# LM13700_v2.net
KiCad netlist of a schematic drawn in EAGLE
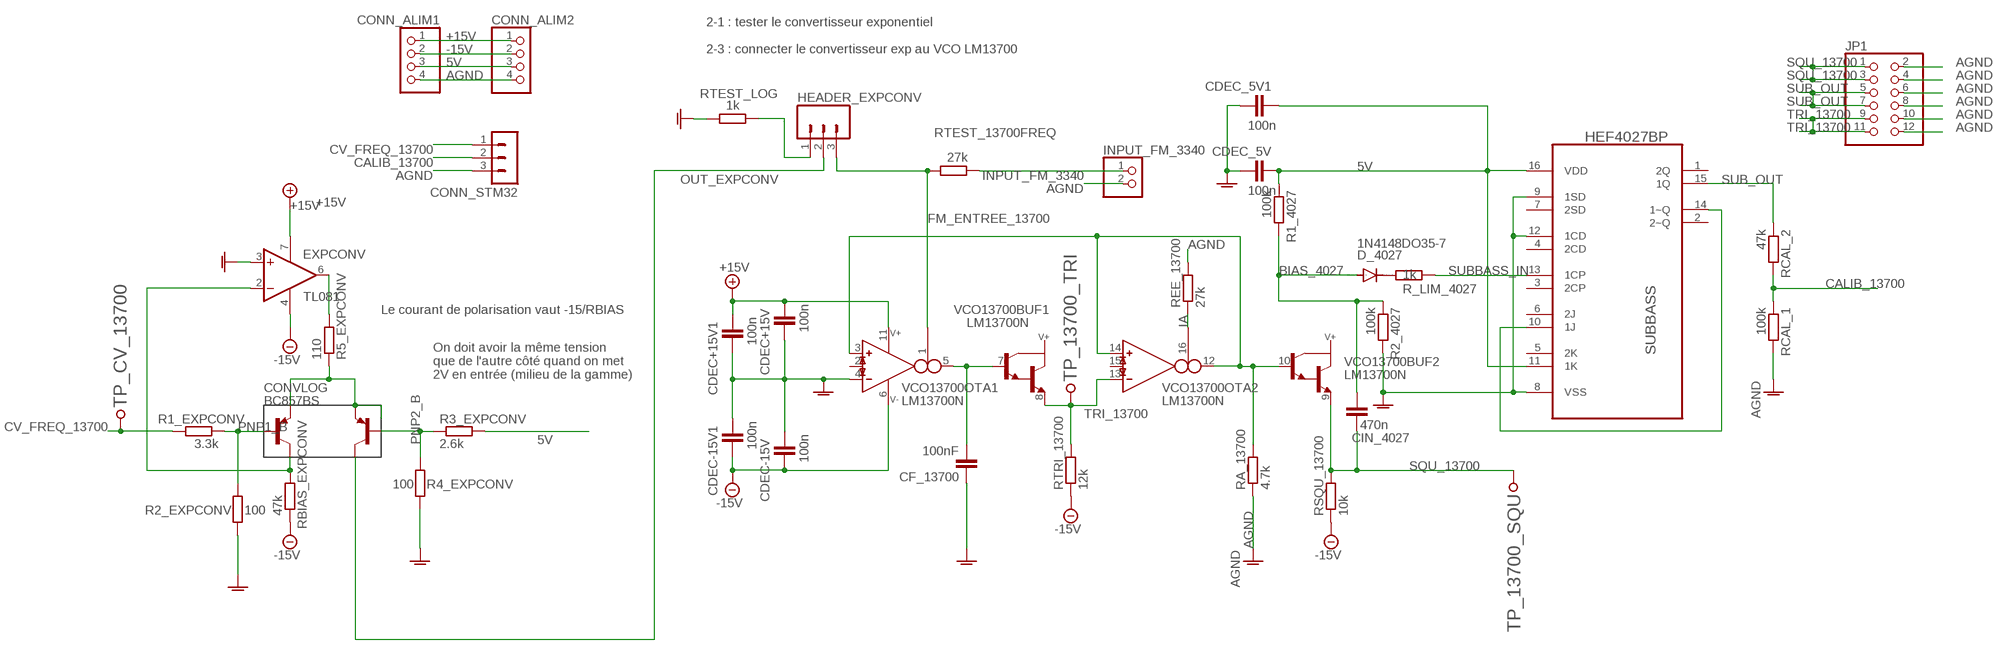
[diagram p0: schematic, sheet 1]

(export (version "E")
  (design (tool "Eeschema 10.0.6"))
  (components
    (comp (ref "CDEC+15V")
      (value "100n")
      (footprint "eagle-import:C075-032X103")
      (libsource (lib "eagle-import") (part "C-EU075-032X103"))
    )
    (comp (ref "CDEC+15V1")
      (value "100n")
      (footprint "eagle-import:C050-025X075")
      (libsource (lib "eagle-import") (part "C-EU050-025X075"))
    )
    (comp (ref "CDEC-15V")
      (value "100n")
      (footprint "eagle-import:C050-025X075")
      (libsource (lib "eagle-import") (part "C-EU050-025X075"))
    )
    (comp (ref "CDEC-15V1")
      (value "100n")
      (footprint "eagle-import:C075-032X103")
      (libsource (lib "eagle-import") (part "C-EU075-032X103"))
    )
    (comp (ref "CDEC_5V")
      (value "100n")
      (footprint "eagle-import:C050-025X075")
      (libsource (lib "eagle-import") (part "C-EU050-025X075"))
    )
    (comp (ref "CDEC_5V1")
      (value "100n")
      (footprint "eagle-import:C050-025X075")
      (libsource (lib "eagle-import") (part "C-EU050-025X075"))
    )
    (comp (ref "CF_13700")
      (value "100nF")
      (footprint "eagle-import:C050-025X075")
      (libsource (lib "eagle-import") (part "C-EU050-025X075"))
    )
    (comp (ref "CIN_4027")
      (value "470n")
      (footprint "eagle-import:C050-025X075")
      (libsource (lib "eagle-import") (part "C-EU050-025X075"))
    )
    (comp (ref "CONN_ALIM1")
      (value "PINHD-1X4")
      (footprint "eagle-import:1X04")
      (libsource (lib "eagle-import") (part "PINHD-1X4"))
    )
    (comp (ref "CONN_ALIM2")
      (value "PINHD-1X4")
      (footprint "eagle-import:1X04")
      (libsource (lib "eagle-import") (part "PINHD-1X4"))
    )
    (comp (ref "CONN_STM32")
      (value "MA03-1")
      (footprint "eagle-import:MA03-1")
      (libsource (lib "eagle-import") (part "MA03-1"))
    )
    (comp (ref "CONVLOG")
      (value "BC857BS")
      (footprint "eagle-import:DIL06")
      (libsource (lib "eagle-import") (part "BC857BS"))
    )
    (comp (ref "D_4027")
      (value "1N4148DO35-7")
      (footprint "eagle-import:DO35-7")
      (libsource (lib "eagle-import") (part "1N4148DO35-7"))
    )
    (comp (ref "EXPCONV")
      (value "TL081")
      (footprint "eagle-import:DIL08")
      (libsource (lib "eagle-import") (part "1AMP_P7+4N"))
    )
    (comp (ref "HEADER_EXPCONV")
      (value "M03")
      (footprint "eagle-import:03P")
      (libsource (lib "eagle-import") (part "M03"))
    )
    (comp (ref "INPUT_FM_3340")
      (value "PINHD-1X2")
      (footprint "eagle-import:1X02")
      (libsource (lib "eagle-import") (part "PINHD-1X2"))
    )
    (comp (ref "JP1")
      (value "PINHD-2X6")
      (footprint "eagle-import:2X06")
      (libsource (lib "eagle-import") (part "PINHD-2X6"))
    )
    (comp (ref "R1_4027")
      (value "100k")
      (footprint "eagle-import:0204_7")
      (libsource (lib "eagle-import") (part "R-EU_0204/7"))
    )
    (comp (ref "R1_EXPCONV")
      (value "3.3k")
      (footprint "eagle-import:0204_7")
      (libsource (lib "eagle-import") (part "R-EU_0204/7"))
    )
    (comp (ref "R2_4027")
      (value "100k")
      (footprint "eagle-import:0204_7")
      (libsource (lib "eagle-import") (part "R-EU_0204/7"))
    )
    (comp (ref "R2_EXPCONV")
      (value "100")
      (footprint "eagle-import:0204_7")
      (libsource (lib "eagle-import") (part "R-EU_0204/7"))
    )
    (comp (ref "R3_EXPCONV")
      (value "2.6k")
      (footprint "eagle-import:0204_7")
      (libsource (lib "eagle-import") (part "R-EU_0204/7"))
    )
    (comp (ref "R4_EXPCONV")
      (value "100")
      (footprint "eagle-import:0204_7")
      (libsource (lib "eagle-import") (part "R-EU_0204/7"))
    )
    (comp (ref "R5_EXPCONV")
      (value "110")
      (footprint "eagle-import:0204_7")
      (libsource (lib "eagle-import") (part "R-EU_0204/7"))
    )
    (comp (ref "RA_13700")
      (value "4.7k")
      (footprint "eagle-import:0204_7")
      (libsource (lib "eagle-import") (part "R-EU_0204/7"))
    )
    (comp (ref "RBIAS_EXPCONV")
      (value "47k")
      (footprint "eagle-import:0204_7")
      (libsource (lib "eagle-import") (part "R-EU_0204/7"))
    )
    (comp (ref "RCAL_1")
      (value "100k")
      (footprint "eagle-import:0204_7")
      (libsource (lib "eagle-import") (part "R-EU_0204/7"))
    )
    (comp (ref "RCAL_2")
      (value "47k")
      (footprint "eagle-import:0204_7")
      (libsource (lib "eagle-import") (part "R-EU_0204/7"))
    )
    (comp (ref "REE_13700")
      (value "27k")
      (footprint "eagle-import:0204_7")
      (libsource (lib "eagle-import") (part "R-EU_0204/7"))
    )
    (comp (ref "RSQU_13700")
      (value "10k")
      (footprint "eagle-import:0204_7")
      (libsource (lib "eagle-import") (part "R-EU_0204/7"))
    )
    (comp (ref "RTEST_13700FREQ")
      (value "27k")
      (footprint "eagle-import:0204_7")
      (libsource (lib "eagle-import") (part "R-EU_0204/7"))
    )
    (comp (ref "RTEST_LOG")
      (value "1k")
      (footprint "eagle-import:0204_7")
      (libsource (lib "eagle-import") (part "R-EU_0204/7"))
    )
    (comp (ref "RTRI_13700")
      (value "12k")
      (footprint "eagle-import:0204_7")
      (libsource (lib "eagle-import") (part "R-EU_0204/7"))
    )
    (comp (ref "R_LIM_4027")
      (value "1k")
      (footprint "eagle-import:0204_7")
      (libsource (lib "eagle-import") (part "R-EU_0204/7"))
    )
    (comp (ref "SUBBASS")
      (value "HEF4027BP")
      (footprint "eagle-import:DIP254P762X420-16")
      (fields (field (name "MF") "NXP Semiconductors"))
      (libsource (lib "eagle-import") (part "HEF4027BP"))
    )
    (comp (ref "TP_13700_SQU")
      (value "TESTPOINT")
      (footprint "eagle-import:TESTPOINT_63")
      (libsource (lib "eagle-import") (part "TESTPOINT"))
    )
    (comp (ref "TP_13700_TRI")
      (value "TESTPOINT")
      (footprint "eagle-import:TESTPOINT_63")
      (libsource (lib "eagle-import") (part "TESTPOINT"))
    )
    (comp (ref "TP_CV_13700")
      (value "TESTPOINT")
      (footprint "eagle-import:TESTPOINT_63")
      (libsource (lib "eagle-import") (part "TESTPOINT"))
    )
    (comp (ref "VCO13700")
      (value "LM13700N")
      (footprint "eagle-import:DIL16")
      (libsource (lib "eagle-import") (part "LM13700N"))
    )
  )
  (nets
    (net (code "1") (name "+15V") (class "Default")
      (node (ref "CDEC+15V") (pin "1") (pinfunction "1_1") (pintype "passive"))
      (node (ref "CDEC+15V1") (pin "1") (pinfunction "1_1") (pintype "passive"))
      (node (ref "CONN_ALIM1") (pin "1") (pinfunction "1_1") (pintype "passive"))
      (node (ref "CONN_ALIM2") (pin "1") (pinfunction "1_1") (pintype "passive"))
      (node (ref "EXPCONV") (pin "7") (pinfunction "V+_7") (pintype "power_in"))
      (node (ref "VCO13700") (pin "11") (pinfunction "V+_11") (pintype "power_in"))
    )
    (net (code "2") (name "-15V") (class "Default")
      (node (ref "CDEC-15V") (pin "2") (pinfunction "2_2") (pintype "passive"))
      (node (ref "CDEC-15V1") (pin "2") (pinfunction "2_2") (pintype "passive"))
      (node (ref "CONN_ALIM1") (pin "2") (pinfunction "2_2") (pintype "passive"))
      (node (ref "CONN_ALIM2") (pin "2") (pinfunction "2_2") (pintype "passive"))
      (node (ref "EXPCONV") (pin "4") (pinfunction "V-_4") (pintype "power_in"))
      (node (ref "RBIAS_EXPCONV") (pin "1") (pinfunction "1_1") (pintype "passive"))
      (node (ref "RSQU_13700") (pin "1") (pinfunction "1_1") (pintype "passive"))
      (node (ref "RTRI_13700") (pin "1") (pinfunction "1_1") (pintype "passive"))
      (node (ref "VCO13700") (pin "6") (pinfunction "V-_6") (pintype "power_in"))
    )
    (net (code "3") (name "/5V") (class "Default")
      (node (ref "CDEC_5V") (pin "1") (pinfunction "1_1") (pintype "passive"))
      (node (ref "CDEC_5V1") (pin "1") (pinfunction "1_1") (pintype "passive"))
      (node (ref "CONN_ALIM1") (pin "3") (pinfunction "3_3") (pintype "passive"))
      (node (ref "CONN_ALIM2") (pin "3") (pinfunction "3_3") (pintype "passive"))
      (node (ref "R1_4027") (pin "1") (pinfunction "1_1") (pintype "passive"))
      (node (ref "R3_EXPCONV") (pin "2") (pinfunction "2_2") (pintype "passive"))
      (node (ref "SUBBASS") (pin "11") (pinfunction "1K_11") (pintype "input"))
      (node (ref "SUBBASS") (pin "16") (pinfunction "VDD_16") (pintype "power_in"))
    )
    (net (code "4") (name "/BIAS_4027") (class "Default")
      (node (ref "CIN_4027") (pin "1") (pinfunction "1_1") (pintype "passive"))
      (node (ref "D_4027") (pin "A") (pinfunction "A_A") (pintype "passive"))
      (node (ref "R1_4027") (pin "2") (pinfunction "2_2") (pintype "passive"))
      (node (ref "R2_4027") (pin "1") (pinfunction "1_1") (pintype "passive"))
    )
    (net (code "5") (name "/CALIB_13700") (class "Default")
      (node (ref "CONN_STM32") (pin "2") (pinfunction "2_2") (pintype "passive"))
      (node (ref "RCAL_1") (pin "1") (pinfunction "1_1") (pintype "passive"))
      (node (ref "RCAL_2") (pin "2") (pinfunction "2_2") (pintype "passive"))
    )
    (net (code "6") (name "/CV_FREQ_13700") (class "Default")
      (node (ref "CONN_STM32") (pin "1") (pinfunction "1_1") (pintype "passive"))
      (node (ref "R1_EXPCONV") (pin "2") (pinfunction "2_2") (pintype "passive"))
      (node (ref "TP_CV_13700") (pin "P$1") (pinfunction "P$1_P$1") (pintype "passive"))
    )
    (net (code "7") (name "/FM_ENTREE_13700") (class "Default")
      (node (ref "HEADER_EXPCONV") (pin "3") (pinfunction "3_3") (pintype "passive"))
      (node (ref "RTEST_13700FREQ") (pin "2") (pinfunction "2_2") (pintype "passive"))
      (node (ref "VCO13700") (pin "1") (pinfunction "I_BIAS_1") (pintype "input"))
    )
    (net (code "8") (name "/IA") (class "Default")
      (node (ref "REE_13700") (pin "1") (pinfunction "1_1") (pintype "passive"))
      (node (ref "VCO13700") (pin "16") (pinfunction "I_BIAS_16") (pintype "input"))
    )
    (net (code "9") (name "/INPUT_FM_3340") (class "Default")
      (node (ref "INPUT_FM_3340") (pin "1") (pinfunction "1_1") (pintype "passive"))
      (node (ref "RTEST_13700FREQ") (pin "1") (pinfunction "1_1") (pintype "passive"))
    )
    (net (code "10") (name "/OUT_EXPCONV") (class "Default")
      (node (ref "CONVLOG") (pin "3") (pinfunction "C2_3") (pintype "passive"))
      (node (ref "HEADER_EXPCONV") (pin "2") (pinfunction "2_2") (pintype "passive"))
    )
    (net (code "11") (name "/PNP1_B") (class "Default")
      (node (ref "CONVLOG") (pin "2") (pinfunction "B1_2") (pintype "passive"))
      (node (ref "R1_EXPCONV") (pin "1") (pinfunction "1_1") (pintype "passive"))
      (node (ref "R2_EXPCONV") (pin "1") (pinfunction "1_1") (pintype "passive"))
    )
    (net (code "12") (name "/PNP2_B") (class "Default")
      (node (ref "CONVLOG") (pin "5") (pinfunction "B2_5") (pintype "passive"))
      (node (ref "R3_EXPCONV") (pin "1") (pinfunction "1_1") (pintype "passive"))
      (node (ref "R4_EXPCONV") (pin "1") (pinfunction "1_1") (pintype "passive"))
    )
    (net (code "13") (name "/SQU_13700") (class "Default")
      (node (ref "CIN_4027") (pin "2") (pinfunction "2_2") (pintype "passive"))
      (node (ref "JP1") (pin "1") (pinfunction "1_1") (pintype "passive"))
      (node (ref "JP1") (pin "3") (pinfunction "3_3") (pintype "passive"))
      (node (ref "RSQU_13700") (pin "2") (pinfunction "2_2") (pintype "passive"))
      (node (ref "TP_13700_SQU") (pin "P$1") (pinfunction "P$1_P$1") (pintype "passive"))
      (node (ref "VCO13700") (pin "9") (pinfunction "E_9") (pintype "passive"))
    )
    (net (code "14") (name "/SUBBASS_IN") (class "Default")
      (node (ref "R_LIM_4027") (pin "1") (pinfunction "1_1") (pintype "passive"))
      (node (ref "SUBBASS") (pin "13") (pinfunction "1CP_13") (pintype "input"))
    )
    (net (code "15") (name "/SUB_OUT") (class "Default")
      (node (ref "JP1") (pin "5") (pinfunction "5_5") (pintype "passive"))
      (node (ref "JP1") (pin "7") (pinfunction "7_7") (pintype "passive"))
      (node (ref "RCAL_2") (pin "1") (pinfunction "1_1") (pintype "passive"))
      (node (ref "SUBBASS") (pin "15") (pinfunction "1Q_15") (pintype "output"))
    )
    (net (code "16") (name "/TRI_13700") (class "Default")
      (node (ref "JP1") (pin "11") (pinfunction "11_11") (pintype "passive"))
      (node (ref "JP1") (pin "9") (pinfunction "9_9") (pintype "passive"))
      (node (ref "RTRI_13700") (pin "2") (pinfunction "2_2") (pintype "passive"))
      (node (ref "TP_13700_TRI") (pin "P$1") (pinfunction "P$1_P$1") (pintype "passive"))
      (node (ref "VCO13700") (pin "13") (pinfunction "IN_N_13") (pintype "input"))
      (node (ref "VCO13700") (pin "8") (pinfunction "E_8") (pintype "passive"))
    )
    (net (code "17") (name "AGND") (class "Default")
      (node (ref "CDEC+15V") (pin "2") (pinfunction "2_2") (pintype "passive"))
      (node (ref "CDEC+15V1") (pin "2") (pinfunction "2_2") (pintype "passive"))
      (node (ref "CDEC-15V") (pin "1") (pinfunction "1_1") (pintype "passive"))
      (node (ref "CDEC-15V1") (pin "1") (pinfunction "1_1") (pintype "passive"))
      (node (ref "CDEC_5V") (pin "2") (pinfunction "2_2") (pintype "passive"))
      (node (ref "CDEC_5V1") (pin "2") (pinfunction "2_2") (pintype "passive"))
      (node (ref "CF_13700") (pin "1") (pinfunction "1_1") (pintype "passive"))
      (node (ref "CONN_ALIM1") (pin "4") (pinfunction "4_4") (pintype "passive"))
      (node (ref "CONN_ALIM2") (pin "4") (pinfunction "4_4") (pintype "passive"))
      (node (ref "CONN_STM32") (pin "3") (pinfunction "3_3") (pintype "passive"))
      (node (ref "EXPCONV") (pin "3") (pinfunction "+IN_3") (pintype "input"))
      (node (ref "INPUT_FM_3340") (pin "2") (pinfunction "2_2") (pintype "passive"))
      (node (ref "JP1") (pin "10") (pinfunction "10_10") (pintype "passive"))
      (node (ref "JP1") (pin "12") (pinfunction "12_12") (pintype "passive"))
      (node (ref "JP1") (pin "2") (pinfunction "2_2") (pintype "passive"))
      (node (ref "JP1") (pin "4") (pinfunction "4_4") (pintype "passive"))
      (node (ref "JP1") (pin "6") (pinfunction "6_6") (pintype "passive"))
      (node (ref "JP1") (pin "8") (pinfunction "8_8") (pintype "passive"))
      (node (ref "R2_4027") (pin "2") (pinfunction "2_2") (pintype "passive"))
      (node (ref "R2_EXPCONV") (pin "2") (pinfunction "2_2") (pintype "passive"))
      (node (ref "R4_EXPCONV") (pin "2") (pinfunction "2_2") (pintype "passive"))
      (node (ref "RA_13700") (pin "1") (pinfunction "1_1") (pintype "passive"))
      (node (ref "RCAL_1") (pin "2") (pinfunction "2_2") (pintype "passive"))
      (node (ref "REE_13700") (pin "2") (pinfunction "2_2") (pintype "passive"))
      (node (ref "RTEST_LOG") (pin "2") (pinfunction "2_2") (pintype "passive"))
      (node (ref "SUBBASS") (pin "12") (pinfunction "1CD_12") (pintype "input"))
      (node (ref "SUBBASS") (pin "8") (pinfunction "VSS_8") (pintype "passive"))
      (node (ref "SUBBASS") (pin "9") (pinfunction "1SD_9") (pintype "input"))
      (node (ref "VCO13700") (pin "4") (pinfunction "IN_N_4") (pintype "input"))
    )
    (net (code "18") (name "Net-(CONVLOG-C1)") (class "Default")
      (node (ref "CONVLOG") (pin "6") (pinfunction "C1_6") (pintype "passive"))
      (node (ref "EXPCONV") (pin "2") (pinfunction "-IN_2") (pintype "input"))
      (node (ref "RBIAS_EXPCONV") (pin "2") (pinfunction "2_2") (pintype "passive"))
    )
    (net (code "19") (name "Net-(CONVLOG-E1)") (class "Default")
      (node (ref "CONVLOG") (pin "1") (pinfunction "E1_1") (pintype "passive"))
      (node (ref "CONVLOG") (pin "4") (pinfunction "E2_4") (pintype "passive"))
      (node (ref "R5_EXPCONV") (pin "1") (pinfunction "1_1") (pintype "passive"))
    )
    (net (code "20") (name "Net-(D_4027-PadC)") (class "Default")
      (node (ref "D_4027") (pin "C") (pinfunction "C_C") (pintype "passive"))
      (node (ref "R_LIM_4027") (pin "2") (pinfunction "2_2") (pintype "passive"))
    )
    (net (code "21") (name "Net-(EXPCONV-OUT)") (class "Default")
      (node (ref "EXPCONV") (pin "6") (pinfunction "OUT_6") (pintype "output"))
      (node (ref "R5_EXPCONV") (pin "2") (pinfunction "2_2") (pintype "passive"))
    )
    (net (code "22") (name "Net-(HEADER_EXPCONV-Pad1)") (class "Default")
      (node (ref "HEADER_EXPCONV") (pin "1") (pinfunction "1_1") (pintype "passive"))
      (node (ref "RTEST_LOG") (pin "1") (pinfunction "1_1") (pintype "passive"))
    )
    (net (code "23") (name "Net-(SUBBASS-1J)") (class "Default")
      (node (ref "SUBBASS") (pin "10") (pinfunction "1J_10") (pintype "input"))
      (node (ref "SUBBASS") (pin "14") (pinfunction "1~{Q}_14") (pintype "output"))
    )
    (net (code "24") (name "Net-(VCO13700A-B)") (class "Default")
      (node (ref "CF_13700") (pin "2") (pinfunction "2_2") (pintype "passive"))
      (node (ref "VCO13700") (pin "5") (pinfunction "OUT_5") (pintype "output"))
      (node (ref "VCO13700") (pin "7") (pinfunction "B_7") (pintype "passive"))
    )
    (net (code "25") (name "Net-(VCO13700B-B)") (class "Default")
      (node (ref "RA_13700") (pin "2") (pinfunction "2_2") (pintype "passive"))
      (node (ref "VCO13700") (pin "10") (pinfunction "B_10") (pintype "passive"))
      (node (ref "VCO13700") (pin "12") (pinfunction "OUT_12") (pintype "output"))
      (node (ref "VCO13700") (pin "14") (pinfunction "IN_P_14") (pintype "input"))
      (node (ref "VCO13700") (pin "3") (pinfunction "IN_P_3") (pintype "input"))
    )
    (net (code "26") (name "unconnected-(SUBBASS-2CD-Pad4)") (class "Default")
      (node (ref "SUBBASS") (pin "4") (pinfunction "2CD_4") (pintype "input"))
    )
    (net (code "27") (name "unconnected-(SUBBASS-2CP-Pad3)") (class "Default")
      (node (ref "SUBBASS") (pin "3") (pinfunction "2CP_3") (pintype "input"))
    )
    (net (code "28") (name "unconnected-(SUBBASS-2J-Pad6)") (class "Default")
      (node (ref "SUBBASS") (pin "6") (pinfunction "2J_6") (pintype "input"))
    )
    (net (code "29") (name "unconnected-(SUBBASS-2K-Pad5)") (class "Default")
      (node (ref "SUBBASS") (pin "5") (pinfunction "2K_5") (pintype "input"))
    )
    (net (code "30") (name "unconnected-(SUBBASS-2Q-Pad1)") (class "Default")
      (node (ref "SUBBASS") (pin "1") (pinfunction "2Q_1") (pintype "output"))
    )
    (net (code "31") (name "unconnected-(SUBBASS-2SD-Pad7)") (class "Default")
      (node (ref "SUBBASS") (pin "7") (pinfunction "2SD_7") (pintype "input"))
    )
    (net (code "32") (name "unconnected-(SUBBASS-2~{Q}-Pad2)") (class "Default")
      (node (ref "SUBBASS") (pin "2") (pinfunction "2~{Q}_2") (pintype "output"))
    )
    (net (code "33") (name "unconnected-(VCO13700C-I_DIODE-Pad2)") (class "Default")
      (node (ref "VCO13700") (pin "2") (pinfunction "I_DIODE_2") (pintype "input"))
    )
    (net (code "34") (name "unconnected-(VCO13700D-I_DIODE-Pad15)") (class "Default")
      (node (ref "VCO13700") (pin "15") (pinfunction "I_DIODE_15") (pintype "input"))
    )
  )
)
